# Extrudrboard2-thunk.net
KiCad netlist of a schematic drawn in EAGLE
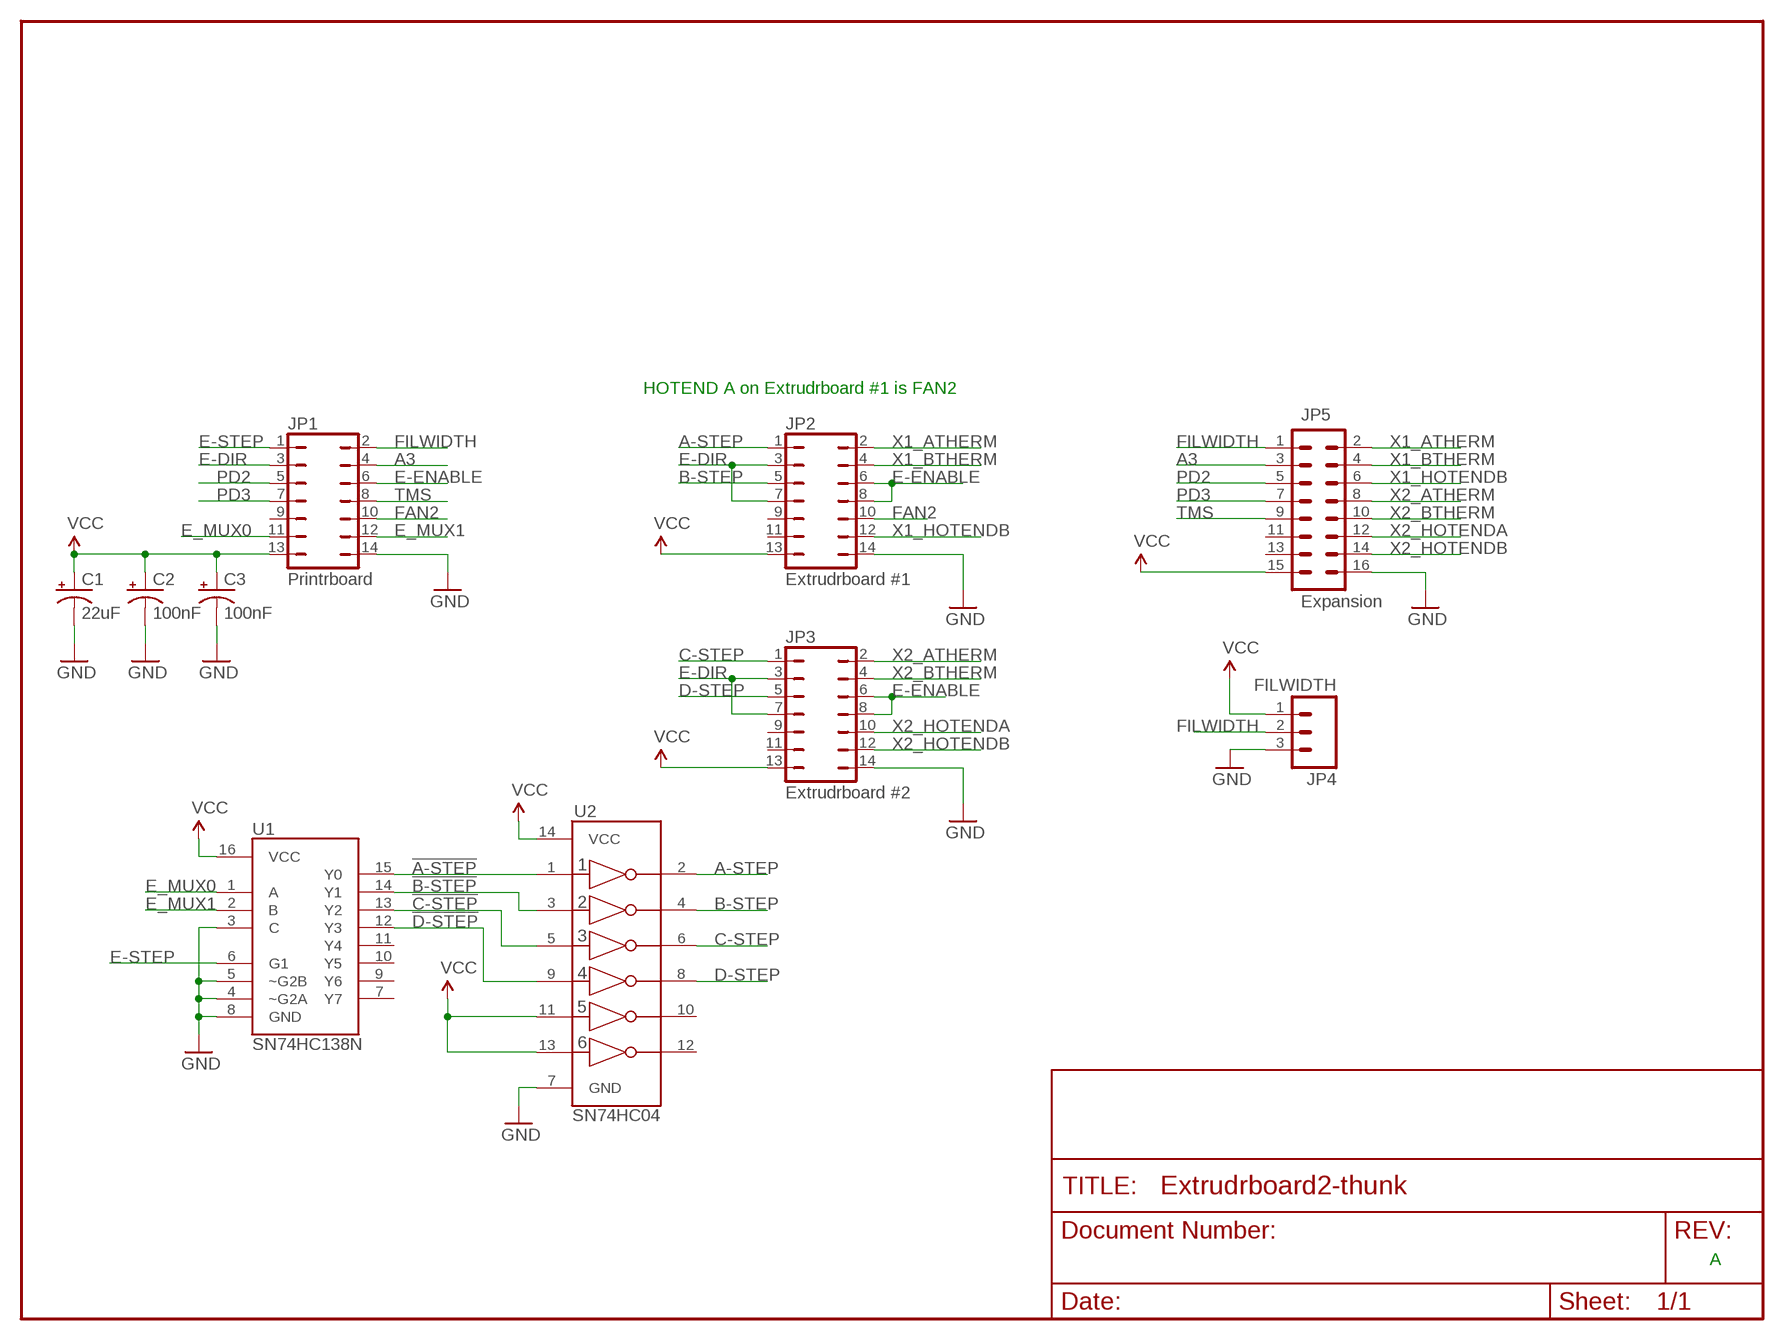
[diagram p0: schematic, sheet 1]

(export (version "E")
  (design (tool "Eeschema 10.0.6"))
  (components
    (comp (ref "C1")
      (value "22uF")
      (footprint "eagle-import:CPOL-RADIAL-100UF-25V")
      (libsource (lib "eagle-import") (part "CAP_POLPTH1"))
    )
    (comp (ref "C2")
      (value "100nF")
      (footprint "eagle-import:CPOL-RADIAL-10UF-25V")
      (libsource (lib "eagle-import") (part "CAP_POLPTH2"))
    )
    (comp (ref "C3")
      (value "100nF")
      (footprint "eagle-import:CPOL-RADIAL-10UF-25V")
      (libsource (lib "eagle-import") (part "CAP_POLPTH2"))
    )
    (comp (ref "JP1")
      (value "Printrboard")
      (footprint "eagle-import:JP7Q")
      (libsource (lib "eagle-import") (part "JP7Q"))
    )
    (comp (ref "JP2")
      (value "Extrudrboard #1")
      (footprint "eagle-import:JP7Q")
      (libsource (lib "eagle-import") (part "JP7Q"))
    )
    (comp (ref "JP3")
      (value "Extrudrboard #2")
      (footprint "eagle-import:JP7Q")
      (libsource (lib "eagle-import") (part "JP7Q"))
    )
    (comp (ref "JP4")
      (value "FILWIDTH")
      (footprint "eagle-import:1X03")
      (libsource (lib "eagle-import") (part "M03PTH"))
    )
    (comp (ref "JP5")
      (value "Expansion")
      (footprint "eagle-import:2X8")
      (libsource (lib "eagle-import") (part "M08X2"))
    )
    (comp (ref "U1")
      (value "SN74HC138N")
      (footprint "eagle-import:DIL16")
      (libsource (lib "eagle-import") (part "M74HC238"))
    )
    (comp (ref "U2")
      (value "SN74HC04")
      (footprint "eagle-import:DIL14")
      (libsource (lib "eagle-import") (part "74HC04_HEX_INVERTER"))
    )
  )
  (nets
    (net (code "1") (name "/A-STEP") (class "Default")
      (node (ref "JP2") (pin "1") (pinfunction "1_1") (pintype "passive"))
      (node (ref "U2") (pin "2") (pinfunction "1Y_2") (pintype "output"))
    )
    (net (code "2") (name "/A3") (class "Default")
      (node (ref "JP1") (pin "4") (pinfunction "4_4") (pintype "passive"))
      (node (ref "JP5") (pin "3") (pinfunction "3_3") (pintype "passive"))
    )
    (net (code "3") (name "/B-STEP") (class "Default")
      (node (ref "JP2") (pin "5") (pinfunction "5_5") (pintype "passive"))
      (node (ref "U2") (pin "4") (pinfunction "2Y_4") (pintype "output"))
    )
    (net (code "4") (name "/C-STEP") (class "Default")
      (node (ref "JP3") (pin "1") (pinfunction "1_1") (pintype "passive"))
      (node (ref "U2") (pin "6") (pinfunction "3Y_6") (pintype "output"))
    )
    (net (code "5") (name "/D-STEP") (class "Default")
      (node (ref "JP3") (pin "5") (pinfunction "5_5") (pintype "passive"))
      (node (ref "U2") (pin "8") (pinfunction "4Y_8") (pintype "output"))
    )
    (net (code "6") (name "/E-DIR") (class "Default")
      (node (ref "JP1") (pin "3") (pinfunction "3_3") (pintype "passive"))
      (node (ref "JP2") (pin "3") (pinfunction "3_3") (pintype "passive"))
      (node (ref "JP2") (pin "7") (pinfunction "7_7") (pintype "passive"))
      (node (ref "JP3") (pin "3") (pinfunction "3_3") (pintype "passive"))
      (node (ref "JP3") (pin "7") (pinfunction "7_7") (pintype "passive"))
    )
    (net (code "7") (name "/E-ENABLE") (class "Default")
      (node (ref "JP1") (pin "6") (pinfunction "6_6") (pintype "passive"))
      (node (ref "JP2") (pin "6") (pinfunction "6_6") (pintype "passive"))
      (node (ref "JP2") (pin "8") (pinfunction "8_8") (pintype "passive"))
      (node (ref "JP3") (pin "6") (pinfunction "6_6") (pintype "passive"))
      (node (ref "JP3") (pin "8") (pinfunction "8_8") (pintype "passive"))
    )
    (net (code "8") (name "/E-STEP") (class "Default")
      (node (ref "JP1") (pin "1") (pinfunction "1_1") (pintype "passive"))
      (node (ref "U1") (pin "6") (pinfunction "G1_6") (pintype "bidirectional"))
    )
    (net (code "9") (name "/E_MUX0") (class "Default")
      (node (ref "JP1") (pin "11") (pinfunction "11_11") (pintype "passive"))
      (node (ref "U1") (pin "1") (pinfunction "A_1") (pintype "bidirectional"))
    )
    (net (code "10") (name "/E_MUX1") (class "Default")
      (node (ref "JP1") (pin "12") (pinfunction "12_12") (pintype "passive"))
      (node (ref "U1") (pin "2") (pinfunction "B_2") (pintype "bidirectional"))
    )
    (net (code "11") (name "/FAN2") (class "Default")
      (node (ref "JP1") (pin "10") (pinfunction "10_10") (pintype "passive"))
      (node (ref "JP2") (pin "10") (pinfunction "10_10") (pintype "passive"))
    )
    (net (code "12") (name "/FILWIDTH") (class "Default")
      (node (ref "JP1") (pin "2") (pinfunction "2_2") (pintype "passive"))
      (node (ref "JP4") (pin "2") (pinfunction "2_2") (pintype "passive"))
      (node (ref "JP5") (pin "1") (pinfunction "1_1") (pintype "passive"))
    )
    (net (code "13") (name "/PD2") (class "Default")
      (node (ref "JP1") (pin "5") (pinfunction "5_5") (pintype "passive"))
      (node (ref "JP5") (pin "5") (pinfunction "5_5") (pintype "passive"))
    )
    (net (code "14") (name "/PD3") (class "Default")
      (node (ref "JP1") (pin "7") (pinfunction "7_7") (pintype "passive"))
      (node (ref "JP5") (pin "7") (pinfunction "7_7") (pintype "passive"))
    )
    (net (code "15") (name "/TMS") (class "Default")
      (node (ref "JP1") (pin "8") (pinfunction "8_8") (pintype "passive"))
      (node (ref "JP5") (pin "9") (pinfunction "9_9") (pintype "passive"))
    )
    (net (code "16") (name "/X1_ATHERM") (class "Default")
      (node (ref "JP2") (pin "2") (pinfunction "2_2") (pintype "passive"))
      (node (ref "JP5") (pin "2") (pinfunction "2_2") (pintype "passive"))
    )
    (net (code "17") (name "/X1_BTHERM") (class "Default")
      (node (ref "JP2") (pin "4") (pinfunction "4_4") (pintype "passive"))
      (node (ref "JP5") (pin "4") (pinfunction "4_4") (pintype "passive"))
    )
    (net (code "18") (name "/X1_HOTENDB") (class "Default")
      (node (ref "JP2") (pin "12") (pinfunction "12_12") (pintype "passive"))
      (node (ref "JP5") (pin "6") (pinfunction "6_6") (pintype "passive"))
    )
    (net (code "19") (name "/X2_ATHERM") (class "Default")
      (node (ref "JP3") (pin "2") (pinfunction "2_2") (pintype "passive"))
      (node (ref "JP5") (pin "8") (pinfunction "8_8") (pintype "passive"))
    )
    (net (code "20") (name "/X2_BTHERM") (class "Default")
      (node (ref "JP3") (pin "4") (pinfunction "4_4") (pintype "passive"))
      (node (ref "JP5") (pin "10") (pinfunction "10_10") (pintype "passive"))
    )
    (net (code "21") (name "/X2_HOTENDA") (class "Default")
      (node (ref "JP3") (pin "10") (pinfunction "10_10") (pintype "passive"))
      (node (ref "JP5") (pin "12") (pinfunction "12_12") (pintype "passive"))
    )
    (net (code "22") (name "/X2_HOTENDB") (class "Default")
      (node (ref "JP3") (pin "12") (pinfunction "12_12") (pintype "passive"))
      (node (ref "JP5") (pin "14") (pinfunction "14_14") (pintype "passive"))
    )
    (net (code "23") (name "/~{A-STEP}") (class "Default")
      (node (ref "U1") (pin "15") (pinfunction "Y0_15") (pintype "bidirectional"))
      (node (ref "U2") (pin "1") (pinfunction "1A_1") (pintype "input"))
    )
    (net (code "24") (name "/~{B-STEP}") (class "Default")
      (node (ref "U1") (pin "14") (pinfunction "Y1_14") (pintype "bidirectional"))
      (node (ref "U2") (pin "3") (pinfunction "2A_3") (pintype "input"))
    )
    (net (code "25") (name "/~{C-STEP}") (class "Default")
      (node (ref "U1") (pin "13") (pinfunction "Y2_13") (pintype "bidirectional"))
      (node (ref "U2") (pin "5") (pinfunction "3A_5") (pintype "input"))
    )
    (net (code "26") (name "/~{D-STEP}") (class "Default")
      (node (ref "U1") (pin "12") (pinfunction "Y3_12") (pintype "bidirectional"))
      (node (ref "U2") (pin "9") (pinfunction "4A_9") (pintype "input"))
    )
    (net (code "27") (name "GND") (class "Default")
      (node (ref "C1") (pin "2") (pinfunction "-_2") (pintype "passive"))
      (node (ref "C2") (pin "2") (pinfunction "-_2") (pintype "passive"))
      (node (ref "C3") (pin "2") (pinfunction "-_2") (pintype "passive"))
      (node (ref "JP1") (pin "14") (pinfunction "14_14") (pintype "passive"))
      (node (ref "JP2") (pin "14") (pinfunction "14_14") (pintype "passive"))
      (node (ref "JP3") (pin "14") (pinfunction "14_14") (pintype "passive"))
      (node (ref "JP4") (pin "3") (pinfunction "3_3") (pintype "passive"))
      (node (ref "JP5") (pin "16") (pinfunction "16_16") (pintype "passive"))
      (node (ref "U1") (pin "3") (pinfunction "C_3") (pintype "bidirectional"))
      (node (ref "U1") (pin "4") (pinfunction "~{G2A}_4") (pintype "bidirectional"))
      (node (ref "U1") (pin "5") (pinfunction "~{G2B}_5") (pintype "bidirectional"))
      (node (ref "U1") (pin "8") (pinfunction "GND_8") (pintype "bidirectional"))
      (node (ref "U2") (pin "7") (pinfunction "GND_7") (pintype "power_in"))
    )
    (net (code "28") (name "VCC") (class "Default")
      (node (ref "C1") (pin "1") (pinfunction "+_1") (pintype "passive"))
      (node (ref "C2") (pin "1") (pinfunction "+_1") (pintype "passive"))
      (node (ref "C3") (pin "1") (pinfunction "+_1") (pintype "passive"))
      (node (ref "JP1") (pin "13") (pinfunction "13_13") (pintype "passive"))
      (node (ref "JP2") (pin "13") (pinfunction "13_13") (pintype "passive"))
      (node (ref "JP3") (pin "13") (pinfunction "13_13") (pintype "passive"))
      (node (ref "JP4") (pin "1") (pinfunction "1_1") (pintype "passive"))
      (node (ref "JP5") (pin "15") (pinfunction "15_15") (pintype "passive"))
      (node (ref "U1") (pin "16") (pinfunction "VCC_16") (pintype "bidirectional"))
      (node (ref "U2") (pin "11") (pinfunction "5A_11") (pintype "input"))
      (node (ref "U2") (pin "13") (pinfunction "6A_13") (pintype "input"))
      (node (ref "U2") (pin "14") (pinfunction "VCC_14") (pintype "power_in"))
    )
    (net (code "29") (name "unconnected-(JP1-Pad9)") (class "Default")
      (node (ref "JP1") (pin "9") (pinfunction "9_9") (pintype "passive"))
    )
    (net (code "30") (name "unconnected-(JP2-Pad9)") (class "Default")
      (node (ref "JP2") (pin "9") (pinfunction "9_9") (pintype "passive"))
    )
    (net (code "31") (name "unconnected-(JP2-Pad11)") (class "Default")
      (node (ref "JP2") (pin "11") (pinfunction "11_11") (pintype "passive"))
    )
    (net (code "32") (name "unconnected-(JP3-Pad9)") (class "Default")
      (node (ref "JP3") (pin "9") (pinfunction "9_9") (pintype "passive"))
    )
    (net (code "33") (name "unconnected-(JP3-Pad11)") (class "Default")
      (node (ref "JP3") (pin "11") (pinfunction "11_11") (pintype "passive"))
    )
    (net (code "34") (name "unconnected-(JP5-Pad11)") (class "Default")
      (node (ref "JP5") (pin "11") (pinfunction "11_11") (pintype "passive"))
    )
    (net (code "35") (name "unconnected-(JP5-Pad13)") (class "Default")
      (node (ref "JP5") (pin "13") (pinfunction "13_13") (pintype "passive"))
    )
    (net (code "36") (name "unconnected-(U1-Y4-Pad11)") (class "Default")
      (node (ref "U1") (pin "11") (pinfunction "Y4_11") (pintype "bidirectional"))
    )
    (net (code "37") (name "unconnected-(U1-Y5-Pad10)") (class "Default")
      (node (ref "U1") (pin "10") (pinfunction "Y5_10") (pintype "bidirectional"))
    )
    (net (code "38") (name "unconnected-(U1-Y6-Pad9)") (class "Default")
      (node (ref "U1") (pin "9") (pinfunction "Y6_9") (pintype "bidirectional"))
    )
    (net (code "39") (name "unconnected-(U1-Y7-Pad7)") (class "Default")
      (node (ref "U1") (pin "7") (pinfunction "Y7_7") (pintype "bidirectional"))
    )
    (net (code "40") (name "unconnected-(U2-5Y-Pad10)") (class "Default")
      (node (ref "U2") (pin "10") (pinfunction "5Y_10") (pintype "output"))
    )
    (net (code "41") (name "unconnected-(U2-6Y-Pad12)") (class "Default")
      (node (ref "U2") (pin "12") (pinfunction "6Y_12") (pintype "output"))
    )
  )
)
